# TLC5940ControlBoard.net
KiCad netlist of a schematic drawn in Altium Designer
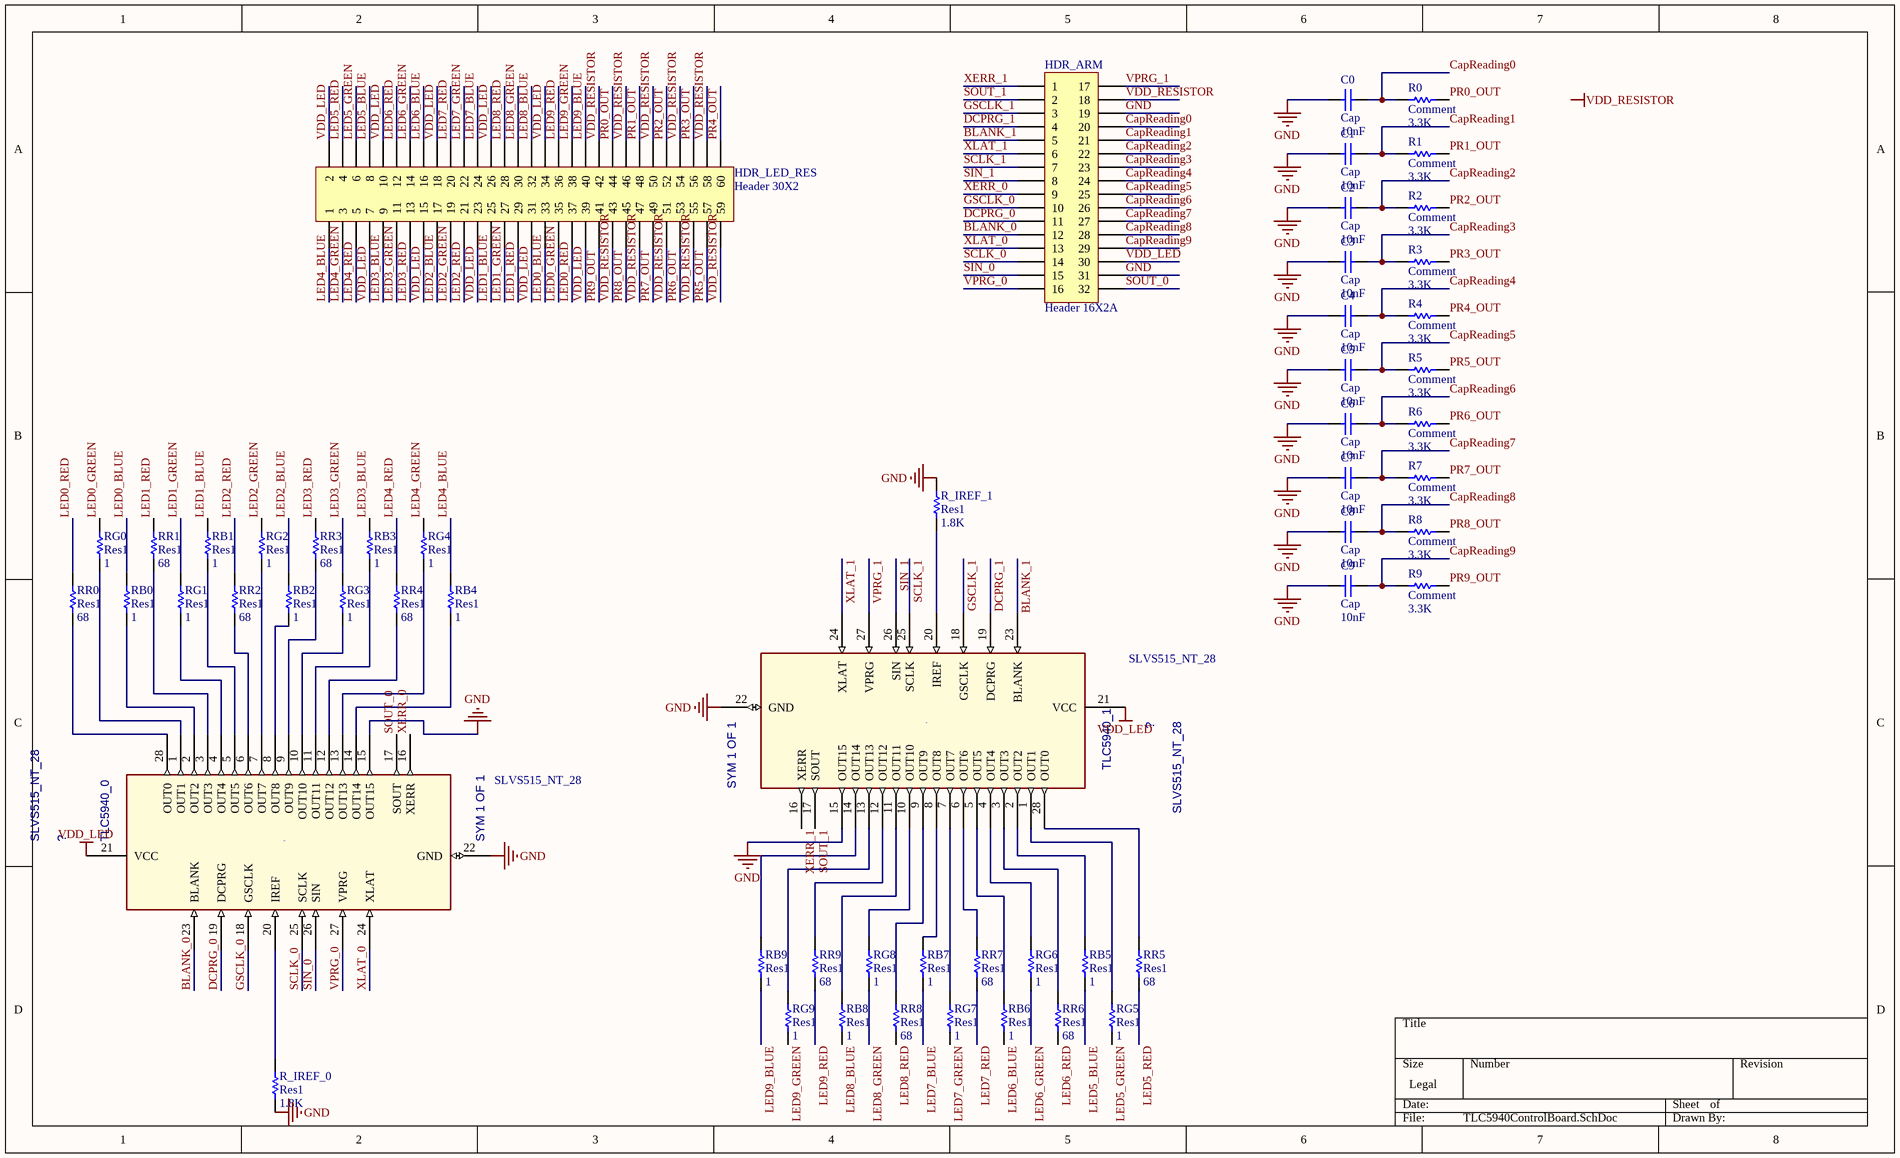
[diagram p0: TLC5940ControlBoard.SchDoc]

(export (version "E")
  (design (tool "Eeschema 10.0.6"))
  (components
    (comp (ref "C0")
      (value "Cap")
      (footprint "CAPR2.54-5.1x3.2")
      (description "Capacitor")
      (fields (field (name "ALTIUM_VALUE") "10nF") (field (name "PUBLISHER") "Altium Limited"))
      (libsource (lib "Miscellaneous Devices") (part "Cap"))
    )
    (comp (ref "C1")
      (value "Cap")
      (footprint "CAPR2.54-5.1x3.2")
      (description "Capacitor")
      (fields (field (name "ALTIUM_VALUE") "10nF") (field (name "PUBLISHER") "Altium Limited"))
      (libsource (lib "Miscellaneous Devices") (part "Cap"))
    )
    (comp (ref "C2")
      (value "Cap")
      (footprint "CAPR2.54-5.1x3.2")
      (description "Capacitor")
      (fields (field (name "ALTIUM_VALUE") "10nF") (field (name "PUBLISHER") "Altium Limited"))
      (libsource (lib "Miscellaneous Devices") (part "Cap"))
    )
    (comp (ref "C3")
      (value "Cap")
      (footprint "CAPR2.54-5.1x3.2")
      (description "Capacitor")
      (fields (field (name "ALTIUM_VALUE") "10nF") (field (name "PUBLISHER") "Altium Limited"))
      (libsource (lib "Miscellaneous Devices") (part "Cap"))
    )
    (comp (ref "C4")
      (value "Cap")
      (footprint "CAPR2.54-5.1x3.2")
      (description "Capacitor")
      (fields (field (name "ALTIUM_VALUE") "10nF") (field (name "PUBLISHER") "Altium Limited"))
      (libsource (lib "Miscellaneous Devices") (part "Cap"))
    )
    (comp (ref "C5")
      (value "Cap")
      (footprint "CAPR2.54-5.1x3.2")
      (description "Capacitor")
      (fields (field (name "ALTIUM_VALUE") "10nF") (field (name "PUBLISHER") "Altium Limited"))
      (libsource (lib "Miscellaneous Devices") (part "Cap"))
    )
    (comp (ref "C6")
      (value "Cap")
      (footprint "CAPR2.54-5.1x3.2")
      (description "Capacitor")
      (fields (field (name "ALTIUM_VALUE") "10nF") (field (name "PUBLISHER") "Altium Limited"))
      (libsource (lib "Miscellaneous Devices") (part "Cap"))
    )
    (comp (ref "C7")
      (value "Cap")
      (footprint "CAPR2.54-5.1x3.2")
      (description "Capacitor")
      (fields (field (name "ALTIUM_VALUE") "10nF") (field (name "PUBLISHER") "Altium Limited"))
      (libsource (lib "Miscellaneous Devices") (part "Cap"))
    )
    (comp (ref "C8")
      (value "Cap")
      (footprint "CAPR2.54-5.1x3.2")
      (description "Capacitor")
      (fields (field (name "ALTIUM_VALUE") "10nF") (field (name "PUBLISHER") "Altium Limited"))
      (libsource (lib "Miscellaneous Devices") (part "Cap"))
    )
    (comp (ref "C9")
      (value "Cap")
      (footprint "CAPR2.54-5.1x3.2")
      (description "Capacitor")
      (fields (field (name "ALTIUM_VALUE") "10nF") (field (name "PUBLISHER") "Altium Limited"))
      (libsource (lib "Miscellaneous Devices") (part "Cap"))
    )
    (comp (ref "HDR_ARM")
      (value "Header 16X2A")
      (footprint "HDR2X16_CEN")
      (description "Header, 16-Pin, Dual row")
      (fields (field (name "PUBLISHER") "Altium Limited"))
      (libsource (lib "Miscellaneous Connectors") (part "Header 16X2A"))
    )
    (comp (ref "HDR_LED_RES")
      (value "Header 30X2")
      (footprint "HDR2X30")
      (description "Header, 30-Pin, Dual row")
      (fields (field (name "PUBLISHER") "Altium Limited"))
      (libsource (lib "Miscellaneous Connectors") (part "Header 30X2"))
    )
    (comp (ref "R0")
      (value "Comment")
      (footprint "AXIAL-0.3")
      (description "Resistor")
      (fields (field (name "ALTIUM_VALUE") "3.3K") (field (name "PUBLISHER") "Altium Limited"))
      (libsource (lib "Miscellaneous Devices") (part "Res1"))
    )
    (comp (ref "R1")
      (value "Comment")
      (footprint "AXIAL-0.3")
      (description "Resistor")
      (fields (field (name "ALTIUM_VALUE") "3.3K") (field (name "PUBLISHER") "Altium Limited"))
      (libsource (lib "Miscellaneous Devices") (part "Res1"))
    )
    (comp (ref "R2")
      (value "Comment")
      (footprint "AXIAL-0.3")
      (description "Resistor")
      (fields (field (name "ALTIUM_VALUE") "3.3K") (field (name "PUBLISHER") "Altium Limited"))
      (libsource (lib "Miscellaneous Devices") (part "Res1"))
    )
    (comp (ref "R3")
      (value "Comment")
      (footprint "AXIAL-0.3")
      (description "Resistor")
      (fields (field (name "ALTIUM_VALUE") "3.3K") (field (name "PUBLISHER") "Altium Limited"))
      (libsource (lib "Miscellaneous Devices") (part "Res1"))
    )
    (comp (ref "R4")
      (value "Comment")
      (footprint "AXIAL-0.3")
      (description "Resistor")
      (fields (field (name "ALTIUM_VALUE") "3.3K") (field (name "PUBLISHER") "Altium Limited"))
      (libsource (lib "Miscellaneous Devices") (part "Res1"))
    )
    (comp (ref "R5")
      (value "Comment")
      (footprint "AXIAL-0.3")
      (description "Resistor")
      (fields (field (name "ALTIUM_VALUE") "3.3K") (field (name "PUBLISHER") "Altium Limited"))
      (libsource (lib "Miscellaneous Devices") (part "Res1"))
    )
    (comp (ref "R6")
      (value "Comment")
      (footprint "AXIAL-0.3")
      (description "Resistor")
      (fields (field (name "ALTIUM_VALUE") "3.3K") (field (name "PUBLISHER") "Altium Limited"))
      (libsource (lib "Miscellaneous Devices") (part "Res1"))
    )
    (comp (ref "R7")
      (value "Comment")
      (footprint "AXIAL-0.3")
      (description "Resistor")
      (fields (field (name "ALTIUM_VALUE") "3.3K") (field (name "PUBLISHER") "Altium Limited"))
      (libsource (lib "Miscellaneous Devices") (part "Res1"))
    )
    (comp (ref "R8")
      (value "Comment")
      (footprint "AXIAL-0.3")
      (description "Resistor")
      (fields (field (name "ALTIUM_VALUE") "3.3K") (field (name "PUBLISHER") "Altium Limited"))
      (libsource (lib "Miscellaneous Devices") (part "Res1"))
    )
    (comp (ref "R9")
      (value "Comment")
      (footprint "AXIAL-0.3")
      (description "Resistor")
      (fields (field (name "ALTIUM_VALUE") "3.3K") (field (name "PUBLISHER") "Altium Limited"))
      (libsource (lib "Miscellaneous Devices") (part "Res1"))
    )
    (comp (ref "RB0")
      (value "Res1")
      (footprint "AXIAL-0.3")
      (description "Resistor")
      (fields (field (name "ALTIUM_VALUE") "1") (field (name "PUBLISHER") "Altium Limited"))
      (libsource (lib "Miscellaneous Devices") (part "Res1"))
    )
    (comp (ref "RB1")
      (value "Res1")
      (footprint "AXIAL-0.3")
      (description "Resistor")
      (fields (field (name "ALTIUM_VALUE") "1") (field (name "PUBLISHER") "Altium Limited"))
      (libsource (lib "Miscellaneous Devices") (part "Res1"))
    )
    (comp (ref "RB2")
      (value "Res1")
      (footprint "AXIAL-0.3")
      (description "Resistor")
      (fields (field (name "ALTIUM_VALUE") "1") (field (name "PUBLISHER") "Altium Limited"))
      (libsource (lib "Miscellaneous Devices") (part "Res1"))
    )
    (comp (ref "RB3")
      (value "Res1")
      (footprint "AXIAL-0.3")
      (description "Resistor")
      (fields (field (name "ALTIUM_VALUE") "1") (field (name "PUBLISHER") "Altium Limited"))
      (libsource (lib "Miscellaneous Devices") (part "Res1"))
    )
    (comp (ref "RB4")
      (value "Res1")
      (footprint "AXIAL-0.3")
      (description "Resistor")
      (fields (field (name "ALTIUM_VALUE") "1") (field (name "PUBLISHER") "Altium Limited"))
      (libsource (lib "Miscellaneous Devices") (part "Res1"))
    )
    (comp (ref "RB5")
      (value "Res1")
      (footprint "AXIAL-0.3")
      (description "Resistor")
      (fields (field (name "ALTIUM_VALUE") "1") (field (name "PUBLISHER") "Altium Limited"))
      (libsource (lib "Miscellaneous Devices") (part "Res1"))
    )
    (comp (ref "RB6")
      (value "Res1")
      (footprint "AXIAL-0.3")
      (description "Resistor")
      (fields (field (name "ALTIUM_VALUE") "1") (field (name "PUBLISHER") "Altium Limited"))
      (libsource (lib "Miscellaneous Devices") (part "Res1"))
    )
    (comp (ref "RB7")
      (value "Res1")
      (footprint "AXIAL-0.3")
      (description "Resistor")
      (fields (field (name "ALTIUM_VALUE") "1") (field (name "PUBLISHER") "Altium Limited"))
      (libsource (lib "Miscellaneous Devices") (part "Res1"))
    )
    (comp (ref "RB8")
      (value "Res1")
      (footprint "AXIAL-0.3")
      (description "Resistor")
      (fields (field (name "ALTIUM_VALUE") "1") (field (name "PUBLISHER") "Altium Limited"))
      (libsource (lib "Miscellaneous Devices") (part "Res1"))
    )
    (comp (ref "RB9")
      (value "Res1")
      (footprint "AXIAL-0.3")
      (description "Resistor")
      (fields (field (name "ALTIUM_VALUE") "1") (field (name "PUBLISHER") "Altium Limited"))
      (libsource (lib "Miscellaneous Devices") (part "Res1"))
    )
    (comp (ref "RG0")
      (value "Res1")
      (footprint "AXIAL-0.3")
      (description "Resistor")
      (fields (field (name "ALTIUM_VALUE") "1") (field (name "PUBLISHER") "Altium Limited"))
      (libsource (lib "Miscellaneous Devices") (part "Res1"))
    )
    (comp (ref "RG1")
      (value "Res1")
      (footprint "AXIAL-0.3")
      (description "Resistor")
      (fields (field (name "ALTIUM_VALUE") "1") (field (name "PUBLISHER") "Altium Limited"))
      (libsource (lib "Miscellaneous Devices") (part "Res1"))
    )
    (comp (ref "RG2")
      (value "Res1")
      (footprint "AXIAL-0.3")
      (description "Resistor")
      (fields (field (name "ALTIUM_VALUE") "1") (field (name "PUBLISHER") "Altium Limited"))
      (libsource (lib "Miscellaneous Devices") (part "Res1"))
    )
    (comp (ref "RG3")
      (value "Res1")
      (footprint "AXIAL-0.3")
      (description "Resistor")
      (fields (field (name "ALTIUM_VALUE") "1") (field (name "PUBLISHER") "Altium Limited"))
      (libsource (lib "Miscellaneous Devices") (part "Res1"))
    )
    (comp (ref "RG4")
      (value "Res1")
      (footprint "AXIAL-0.3")
      (description "Resistor")
      (fields (field (name "ALTIUM_VALUE") "1") (field (name "PUBLISHER") "Altium Limited"))
      (libsource (lib "Miscellaneous Devices") (part "Res1"))
    )
    (comp (ref "RG5")
      (value "Res1")
      (footprint "AXIAL-0.3")
      (description "Resistor")
      (fields (field (name "ALTIUM_VALUE") "1") (field (name "PUBLISHER") "Altium Limited"))
      (libsource (lib "Miscellaneous Devices") (part "Res1"))
    )
    (comp (ref "RG6")
      (value "Res1")
      (footprint "AXIAL-0.3")
      (description "Resistor")
      (fields (field (name "ALTIUM_VALUE") "1") (field (name "PUBLISHER") "Altium Limited"))
      (libsource (lib "Miscellaneous Devices") (part "Res1"))
    )
    (comp (ref "RG7")
      (value "Res1")
      (footprint "AXIAL-0.3")
      (description "Resistor")
      (fields (field (name "ALTIUM_VALUE") "1") (field (name "PUBLISHER") "Altium Limited"))
      (libsource (lib "Miscellaneous Devices") (part "Res1"))
    )
    (comp (ref "RG8")
      (value "Res1")
      (footprint "AXIAL-0.3")
      (description "Resistor")
      (fields (field (name "ALTIUM_VALUE") "1") (field (name "PUBLISHER") "Altium Limited"))
      (libsource (lib "Miscellaneous Devices") (part "Res1"))
    )
    (comp (ref "RG9")
      (value "Res1")
      (footprint "AXIAL-0.3")
      (description "Resistor")
      (fields (field (name "ALTIUM_VALUE") "1") (field (name "PUBLISHER") "Altium Limited"))
      (libsource (lib "Miscellaneous Devices") (part "Res1"))
    )
    (comp (ref "RR0")
      (value "Res1")
      (footprint "AXIAL-0.3")
      (description "Resistor")
      (fields (field (name "ALTIUM_VALUE") "68") (field (name "PUBLISHER") "Altium Limited"))
      (libsource (lib "Miscellaneous Devices") (part "Res1"))
    )
    (comp (ref "RR1")
      (value "Res1")
      (footprint "AXIAL-0.3")
      (description "Resistor")
      (fields (field (name "ALTIUM_VALUE") "68") (field (name "PUBLISHER") "Altium Limited"))
      (libsource (lib "Miscellaneous Devices") (part "Res1"))
    )
    (comp (ref "RR2")
      (value "Res1")
      (footprint "AXIAL-0.3")
      (description "Resistor")
      (fields (field (name "ALTIUM_VALUE") "68") (field (name "PUBLISHER") "Altium Limited"))
      (libsource (lib "Miscellaneous Devices") (part "Res1"))
    )
    (comp (ref "RR3")
      (value "Res1")
      (footprint "AXIAL-0.3")
      (description "Resistor")
      (fields (field (name "ALTIUM_VALUE") "68") (field (name "PUBLISHER") "Altium Limited"))
      (libsource (lib "Miscellaneous Devices") (part "Res1"))
    )
    (comp (ref "RR4")
      (value "Res1")
      (footprint "AXIAL-0.3")
      (description "Resistor")
      (fields (field (name "ALTIUM_VALUE") "68") (field (name "PUBLISHER") "Altium Limited"))
      (libsource (lib "Miscellaneous Devices") (part "Res1"))
    )
    (comp (ref "RR5")
      (value "Res1")
      (footprint "AXIAL-0.3")
      (description "Resistor")
      (fields (field (name "ALTIUM_VALUE") "68") (field (name "PUBLISHER") "Altium Limited"))
      (libsource (lib "Miscellaneous Devices") (part "Res1"))
    )
    (comp (ref "RR6")
      (value "Res1")
      (footprint "AXIAL-0.3")
      (description "Resistor")
      (fields (field (name "ALTIUM_VALUE") "68") (field (name "PUBLISHER") "Altium Limited"))
      (libsource (lib "Miscellaneous Devices") (part "Res1"))
    )
    (comp (ref "RR7")
      (value "Res1")
      (footprint "AXIAL-0.3")
      (description "Resistor")
      (fields (field (name "ALTIUM_VALUE") "68") (field (name "PUBLISHER") "Altium Limited"))
      (libsource (lib "Miscellaneous Devices") (part "Res1"))
    )
    (comp (ref "RR8")
      (value "Res1")
      (footprint "AXIAL-0.3")
      (description "Resistor")
      (fields (field (name "ALTIUM_VALUE") "68") (field (name "PUBLISHER") "Altium Limited"))
      (libsource (lib "Miscellaneous Devices") (part "Res1"))
    )
    (comp (ref "RR9")
      (value "Res1")
      (footprint "AXIAL-0.3")
      (description "Resistor")
      (fields (field (name "ALTIUM_VALUE") "68") (field (name "PUBLISHER") "Altium Limited"))
      (libsource (lib "Miscellaneous Devices") (part "Res1"))
    )
    (comp (ref "R_IREF_0")
      (value "Res1")
      (footprint "AXIAL-0.3")
      (description "Resistor")
      (fields (field (name "ALTIUM_VALUE") "1.8K") (field (name "PUBLISHER") "Altium Limited"))
      (libsource (lib "Miscellaneous Devices") (part "Res1"))
    )
    (comp (ref "R_IREF_1")
      (value "Res1")
      (footprint "AXIAL-0.3")
      (description "Resistor")
      (fields (field (name "ALTIUM_VALUE") "1.8K") (field (name "PUBLISHER") "Altium Limited"))
      (libsource (lib "Miscellaneous Devices") (part "Res1"))
    )
    (comp (ref "TLC5940_0")
      (value "SLVS515_NT_28")
      (footprint "NT028")
      (fields
        (field (name "SYMNAME") "SLVS515_NT_28")
        (field (name "REFLOCATION") "?")
        (field (name "BOARDLOCATION") "?")
        (field (name "SLOTXOFY") "SYM 1 OF 1")
      )
      (libsource (lib "SLVS515_NT_28_Library") (part "SLVS515_NT_28"))
    )
    (comp (ref "TLC5940_1")
      (value "SLVS515_NT_28")
      (footprint "NT028")
      (fields
        (field (name "SYMNAME") "SLVS515_NT_28")
        (field (name "REFLOCATION") "?")
        (field (name "BOARDLOCATION") "?")
        (field (name "SLOTXOFY") "SYM 1 OF 1")
      )
      (libsource (lib "") (part "SLVS515_NT_28_1"))
    )
  )
  (nets
    (net (code "1") (name "/BLANK_0") (class "Default")
      (node (ref "HDR_ARM") (pin "12") (pinfunction "12_12") (pintype "passive"))
      (node (ref "TLC5940_0") (pin "23") (pinfunction "BLANK_23") (pintype "input"))
    )
    (net (code "2") (name "/BLANK_1") (class "Default")
      (node (ref "HDR_ARM") (pin "5") (pinfunction "5_5") (pintype "passive"))
      (node (ref "TLC5940_1") (pin "23") (pinfunction "BLANK_23") (pintype "input"))
    )
    (net (code "3") (name "/CapReading0") (class "Default")
      (node (ref "C0") (pin "2") (pinfunction "2_2") (pintype "passive"))
      (node (ref "HDR_ARM") (pin "20") (pinfunction "20_20") (pintype "passive"))
      (node (ref "R0") (pin "1") (pinfunction "1_1") (pintype "passive"))
    )
    (net (code "4") (name "/CapReading1") (class "Default")
      (node (ref "C1") (pin "2") (pinfunction "2_2") (pintype "passive"))
      (node (ref "HDR_ARM") (pin "21") (pinfunction "21_21") (pintype "passive"))
      (node (ref "R1") (pin "1") (pinfunction "1_1") (pintype "passive"))
    )
    (net (code "5") (name "/CapReading2") (class "Default")
      (node (ref "C2") (pin "2") (pinfunction "2_2") (pintype "passive"))
      (node (ref "HDR_ARM") (pin "22") (pinfunction "22_22") (pintype "passive"))
      (node (ref "R2") (pin "1") (pinfunction "1_1") (pintype "passive"))
    )
    (net (code "6") (name "/CapReading3") (class "Default")
      (node (ref "C3") (pin "2") (pinfunction "2_2") (pintype "passive"))
      (node (ref "HDR_ARM") (pin "23") (pinfunction "23_23") (pintype "passive"))
      (node (ref "R3") (pin "1") (pinfunction "1_1") (pintype "passive"))
    )
    (net (code "7") (name "/CapReading4") (class "Default")
      (node (ref "C4") (pin "2") (pinfunction "2_2") (pintype "passive"))
      (node (ref "HDR_ARM") (pin "24") (pinfunction "24_24") (pintype "passive"))
      (node (ref "R4") (pin "1") (pinfunction "1_1") (pintype "passive"))
    )
    (net (code "8") (name "/CapReading5") (class "Default")
      (node (ref "C5") (pin "2") (pinfunction "2_2") (pintype "passive"))
      (node (ref "HDR_ARM") (pin "25") (pinfunction "25_25") (pintype "passive"))
      (node (ref "R5") (pin "1") (pinfunction "1_1") (pintype "passive"))
    )
    (net (code "9") (name "/CapReading6") (class "Default")
      (node (ref "C6") (pin "2") (pinfunction "2_2") (pintype "passive"))
      (node (ref "HDR_ARM") (pin "26") (pinfunction "26_26") (pintype "passive"))
      (node (ref "R6") (pin "1") (pinfunction "1_1") (pintype "passive"))
    )
    (net (code "10") (name "/CapReading7") (class "Default")
      (node (ref "C7") (pin "2") (pinfunction "2_2") (pintype "passive"))
      (node (ref "HDR_ARM") (pin "27") (pinfunction "27_27") (pintype "passive"))
      (node (ref "R7") (pin "1") (pinfunction "1_1") (pintype "passive"))
    )
    (net (code "11") (name "/CapReading8") (class "Default")
      (node (ref "C8") (pin "2") (pinfunction "2_2") (pintype "passive"))
      (node (ref "HDR_ARM") (pin "28") (pinfunction "28_28") (pintype "passive"))
      (node (ref "R8") (pin "1") (pinfunction "1_1") (pintype "passive"))
    )
    (net (code "12") (name "/CapReading9") (class "Default")
      (node (ref "C9") (pin "2") (pinfunction "2_2") (pintype "passive"))
      (node (ref "HDR_ARM") (pin "29") (pinfunction "29_29") (pintype "passive"))
      (node (ref "R9") (pin "1") (pinfunction "1_1") (pintype "passive"))
    )
    (net (code "13") (name "/DCPRG_0") (class "Default")
      (node (ref "HDR_ARM") (pin "11") (pinfunction "11_11") (pintype "passive"))
      (node (ref "TLC5940_0") (pin "19") (pinfunction "DCPRG_19") (pintype "input"))
    )
    (net (code "14") (name "/DCPRG_1") (class "Default")
      (node (ref "HDR_ARM") (pin "4") (pinfunction "4_4") (pintype "passive"))
      (node (ref "TLC5940_1") (pin "19") (pinfunction "DCPRG_19") (pintype "input"))
    )
    (net (code "15") (name "/GSCLK_0") (class "Default")
      (node (ref "HDR_ARM") (pin "10") (pinfunction "10_10") (pintype "passive"))
      (node (ref "TLC5940_0") (pin "18") (pinfunction "GSCLK_18") (pintype "input"))
    )
    (net (code "16") (name "/GSCLK_1") (class "Default")
      (node (ref "HDR_ARM") (pin "3") (pinfunction "3_3") (pintype "passive"))
      (node (ref "TLC5940_1") (pin "18") (pinfunction "GSCLK_18") (pintype "input"))
    )
    (net (code "17") (name "/LED0_BLUE") (class "Default")
      (node (ref "HDR_LED_RES") (pin "33") (pinfunction "33_33") (pintype "passive"))
      (node (ref "RB0") (pin "2") (pinfunction "2_2") (pintype "passive"))
    )
    (net (code "18") (name "/LED0_GREEN") (class "Default")
      (node (ref "HDR_LED_RES") (pin "35") (pinfunction "35_35") (pintype "passive"))
      (node (ref "RG0") (pin "2") (pinfunction "2_2") (pintype "passive"))
    )
    (net (code "19") (name "/LED0_RED") (class "Default")
      (node (ref "HDR_LED_RES") (pin "37") (pinfunction "37_37") (pintype "passive"))
      (node (ref "RR0") (pin "2") (pinfunction "2_2") (pintype "passive"))
    )
    (net (code "20") (name "/LED1_BLUE") (class "Default")
      (node (ref "HDR_LED_RES") (pin "25") (pinfunction "25_25") (pintype "passive"))
      (node (ref "RB1") (pin "2") (pinfunction "2_2") (pintype "passive"))
    )
    (net (code "21") (name "/LED1_GREEN") (class "Default")
      (node (ref "HDR_LED_RES") (pin "27") (pinfunction "27_27") (pintype "passive"))
      (node (ref "RG1") (pin "2") (pinfunction "2_2") (pintype "passive"))
    )
    (net (code "22") (name "/LED1_RED") (class "Default")
      (node (ref "HDR_LED_RES") (pin "29") (pinfunction "29_29") (pintype "passive"))
      (node (ref "RR1") (pin "2") (pinfunction "2_2") (pintype "passive"))
    )
    (net (code "23") (name "/LED2_BLUE") (class "Default")
      (node (ref "HDR_LED_RES") (pin "17") (pinfunction "17_17") (pintype "passive"))
      (node (ref "RB2") (pin "2") (pinfunction "2_2") (pintype "passive"))
    )
    (net (code "24") (name "/LED2_GREEN") (class "Default")
      (node (ref "HDR_LED_RES") (pin "19") (pinfunction "19_19") (pintype "passive"))
      (node (ref "RG2") (pin "2") (pinfunction "2_2") (pintype "passive"))
    )
    (net (code "25") (name "/LED2_RED") (class "Default")
      (node (ref "HDR_LED_RES") (pin "21") (pinfunction "21_21") (pintype "passive"))
      (node (ref "RR2") (pin "2") (pinfunction "2_2") (pintype "passive"))
    )
    (net (code "26") (name "/LED3_BLUE") (class "Default")
      (node (ref "HDR_LED_RES") (pin "9") (pinfunction "9_9") (pintype "passive"))
      (node (ref "RB3") (pin "2") (pinfunction "2_2") (pintype "passive"))
    )
    (net (code "27") (name "/LED3_GREEN") (class "Default")
      (node (ref "HDR_LED_RES") (pin "11") (pinfunction "11_11") (pintype "passive"))
      (node (ref "RG3") (pin "2") (pinfunction "2_2") (pintype "passive"))
    )
    (net (code "28") (name "/LED3_RED") (class "Default")
      (node (ref "HDR_LED_RES") (pin "13") (pinfunction "13_13") (pintype "passive"))
      (node (ref "RR3") (pin "2") (pinfunction "2_2") (pintype "passive"))
    )
    (net (code "29") (name "/LED4_BLUE") (class "Default")
      (node (ref "HDR_LED_RES") (pin "1") (pinfunction "1_1") (pintype "passive"))
      (node (ref "RB4") (pin "2") (pinfunction "2_2") (pintype "passive"))
    )
    (net (code "30") (name "/LED4_GREEN") (class "Default")
      (node (ref "HDR_LED_RES") (pin "3") (pinfunction "3_3") (pintype "passive"))
      (node (ref "RG4") (pin "2") (pinfunction "2_2") (pintype "passive"))
    )
    (net (code "31") (name "/LED4_RED") (class "Default")
      (node (ref "HDR_LED_RES") (pin "5") (pinfunction "5_5") (pintype "passive"))
      (node (ref "RR4") (pin "2") (pinfunction "2_2") (pintype "passive"))
    )
    (net (code "32") (name "/LED5_BLUE") (class "Default")
      (node (ref "HDR_LED_RES") (pin "8") (pinfunction "8_8") (pintype "passive"))
      (node (ref "RB5") (pin "2") (pinfunction "2_2") (pintype "passive"))
    )
    (net (code "33") (name "/LED5_GREEN") (class "Default")
      (node (ref "HDR_LED_RES") (pin "6") (pinfunction "6_6") (pintype "passive"))
      (node (ref "RG5") (pin "2") (pinfunction "2_2") (pintype "passive"))
    )
    (net (code "34") (name "/LED5_RED") (class "Default")
      (node (ref "HDR_LED_RES") (pin "4") (pinfunction "4_4") (pintype "passive"))
      (node (ref "RR5") (pin "2") (pinfunction "2_2") (pintype "passive"))
    )
    (net (code "35") (name "/LED6_BLUE") (class "Default")
      (node (ref "HDR_LED_RES") (pin "16") (pinfunction "16_16") (pintype "passive"))
      (node (ref "RB6") (pin "2") (pinfunction "2_2") (pintype "passive"))
    )
    (net (code "36") (name "/LED6_GREEN") (class "Default")
      (node (ref "HDR_LED_RES") (pin "14") (pinfunction "14_14") (pintype "passive"))
      (node (ref "RG6") (pin "2") (pinfunction "2_2") (pintype "passive"))
    )
    (net (code "37") (name "/LED6_RED") (class "Default")
      (node (ref "HDR_LED_RES") (pin "12") (pinfunction "12_12") (pintype "passive"))
      (node (ref "RR6") (pin "2") (pinfunction "2_2") (pintype "passive"))
    )
    (net (code "38") (name "/LED7_BLUE") (class "Default")
      (node (ref "HDR_LED_RES") (pin "24") (pinfunction "24_24") (pintype "passive"))
      (node (ref "RB7") (pin "2") (pinfunction "2_2") (pintype "passive"))
    )
    (net (code "39") (name "/LED7_GREEN") (class "Default")
      (node (ref "HDR_LED_RES") (pin "22") (pinfunction "22_22") (pintype "passive"))
      (node (ref "RG7") (pin "2") (pinfunction "2_2") (pintype "passive"))
    )
    (net (code "40") (name "/LED7_RED") (class "Default")
      (node (ref "HDR_LED_RES") (pin "20") (pinfunction "20_20") (pintype "passive"))
      (node (ref "RR7") (pin "2") (pinfunction "2_2") (pintype "passive"))
    )
    (net (code "41") (name "/LED8_BLUE") (class "Default")
      (node (ref "HDR_LED_RES") (pin "32") (pinfunction "32_32") (pintype "passive"))
      (node (ref "RB8") (pin "2") (pinfunction "2_2") (pintype "passive"))
    )
    (net (code "42") (name "/LED8_GREEN") (class "Default")
      (node (ref "HDR_LED_RES") (pin "30") (pinfunction "30_30") (pintype "passive"))
      (node (ref "RG8") (pin "2") (pinfunction "2_2") (pintype "passive"))
    )
    (net (code "43") (name "/LED8_RED") (class "Default")
      (node (ref "HDR_LED_RES") (pin "28") (pinfunction "28_28") (pintype "passive"))
      (node (ref "RR8") (pin "2") (pinfunction "2_2") (pintype "passive"))
    )
    (net (code "44") (name "/LED9_BLUE") (class "Default")
      (node (ref "HDR_LED_RES") (pin "40") (pinfunction "40_40") (pintype "passive"))
      (node (ref "RB9") (pin "2") (pinfunction "2_2") (pintype "passive"))
    )
    (net (code "45") (name "/LED9_GREEN") (class "Default")
      (node (ref "HDR_LED_RES") (pin "38") (pinfunction "38_38") (pintype "passive"))
      (node (ref "RG9") (pin "2") (pinfunction "2_2") (pintype "passive"))
    )
    (net (code "46") (name "/LED9_RED") (class "Default")
      (node (ref "HDR_LED_RES") (pin "36") (pinfunction "36_36") (pintype "passive"))
      (node (ref "RR9") (pin "2") (pinfunction "2_2") (pintype "passive"))
    )
    (net (code "47") (name "/PR0_OUT") (class "Default")
      (node (ref "HDR_LED_RES") (pin "44") (pinfunction "44_44") (pintype "passive"))
      (node (ref "R0") (pin "2") (pinfunction "2_2") (pintype "passive"))
    )
    (net (code "48") (name "/PR1_OUT") (class "Default")
      (node (ref "HDR_LED_RES") (pin "48") (pinfunction "48_48") (pintype "passive"))
      (node (ref "R1") (pin "2") (pinfunction "2_2") (pintype "passive"))
    )
    (net (code "49") (name "/PR2_OUT") (class "Default")
      (node (ref "HDR_LED_RES") (pin "52") (pinfunction "52_52") (pintype "passive"))
      (node (ref "R2") (pin "2") (pinfunction "2_2") (pintype "passive"))
    )
    (net (code "50") (name "/PR3_OUT") (class "Default")
      (node (ref "HDR_LED_RES") (pin "56") (pinfunction "56_56") (pintype "passive"))
      (node (ref "R3") (pin "2") (pinfunction "2_2") (pintype "passive"))
    )
    (net (code "51") (name "/PR4_OUT") (class "Default")
      (node (ref "HDR_LED_RES") (pin "60") (pinfunction "60_60") (pintype "passive"))
      (node (ref "R4") (pin "2") (pinfunction "2_2") (pintype "passive"))
    )
    (net (code "52") (name "/PR5_OUT") (class "Default")
      (node (ref "HDR_LED_RES") (pin "57") (pinfunction "57_57") (pintype "passive"))
      (node (ref "R5") (pin "2") (pinfunction "2_2") (pintype "passive"))
    )
    (net (code "53") (name "/PR6_OUT") (class "Default")
      (node (ref "HDR_LED_RES") (pin "53") (pinfunction "53_53") (pintype "passive"))
      (node (ref "R6") (pin "2") (pinfunction "2_2") (pintype "passive"))
    )
    (net (code "54") (name "/PR7_OUT") (class "Default")
      (node (ref "HDR_LED_RES") (pin "49") (pinfunction "49_49") (pintype "passive"))
      (node (ref "R7") (pin "2") (pinfunction "2_2") (pintype "passive"))
    )
    (net (code "55") (name "/PR8_OUT") (class "Default")
      (node (ref "HDR_LED_RES") (pin "45") (pinfunction "45_45") (pintype "passive"))
      (node (ref "R8") (pin "2") (pinfunction "2_2") (pintype "passive"))
    )
    (net (code "56") (name "/PR9_OUT") (class "Default")
      (node (ref "HDR_LED_RES") (pin "41") (pinfunction "41_41") (pintype "passive"))
      (node (ref "R9") (pin "2") (pinfunction "2_2") (pintype "passive"))
    )
    (net (code "57") (name "/SCLK_0") (class "Default")
      (node (ref "HDR_ARM") (pin "14") (pinfunction "14_14") (pintype "passive"))
      (node (ref "TLC5940_0") (pin "25") (pinfunction "SCLK_25") (pintype "input"))
    )
    (net (code "58") (name "/SCLK_1") (class "Default")
      (node (ref "HDR_ARM") (pin "7") (pinfunction "7_7") (pintype "passive"))
      (node (ref "TLC5940_1") (pin "25") (pinfunction "SCLK_25") (pintype "input"))
    )
    (net (code "59") (name "/SIN_0") (class "Default")
      (node (ref "HDR_ARM") (pin "15") (pinfunction "15_15") (pintype "passive"))
      (node (ref "TLC5940_0") (pin "26") (pinfunction "SIN_26") (pintype "input"))
    )
    (net (code "60") (name "/SIN_1") (class "Default")
      (node (ref "HDR_ARM") (pin "8") (pinfunction "8_8") (pintype "passive"))
      (node (ref "TLC5940_1") (pin "26") (pinfunction "SIN_26") (pintype "input"))
    )
    (net (code "61") (name "/SOUT_0") (class "Default")
      (node (ref "HDR_ARM") (pin "32") (pinfunction "32_32") (pintype "passive"))
      (node (ref "TLC5940_0") (pin "17") (pinfunction "SOUT_17") (pintype "output"))
    )
    (net (code "62") (name "/SOUT_1") (class "Default")
      (node (ref "HDR_ARM") (pin "2") (pinfunction "2_2") (pintype "passive"))
      (node (ref "TLC5940_1") (pin "17") (pinfunction "SOUT_17") (pintype "output"))
    )
    (net (code "63") (name "/VPRG_0") (class "Default")
      (node (ref "HDR_ARM") (pin "16") (pinfunction "16_16") (pintype "passive"))
      (node (ref "TLC5940_0") (pin "27") (pinfunction "VPRG_27") (pintype "input"))
    )
    (net (code "64") (name "/VPRG_1") (class "Default")
      (node (ref "HDR_ARM") (pin "17") (pinfunction "17_17") (pintype "passive"))
      (node (ref "TLC5940_1") (pin "27") (pinfunction "VPRG_27") (pintype "input"))
    )
    (net (code "65") (name "/XERR_0") (class "Default")
      (node (ref "HDR_ARM") (pin "9") (pinfunction "9_9") (pintype "passive"))
      (node (ref "TLC5940_0") (pin "16") (pinfunction "XERR_16") (pintype "output"))
    )
    (net (code "66") (name "/XERR_1") (class "Default")
      (node (ref "HDR_ARM") (pin "1") (pinfunction "1_1") (pintype "passive"))
      (node (ref "TLC5940_1") (pin "16") (pinfunction "XERR_16") (pintype "output"))
    )
    (net (code "67") (name "/XLAT_0") (class "Default")
      (node (ref "HDR_ARM") (pin "13") (pinfunction "13_13") (pintype "passive"))
      (node (ref "TLC5940_0") (pin "24") (pinfunction "XLAT_24") (pintype "input"))
    )
    (net (code "68") (name "/XLAT_1") (class "Default")
      (node (ref "HDR_ARM") (pin "6") (pinfunction "6_6") (pintype "passive"))
      (node (ref "TLC5940_1") (pin "24") (pinfunction "XLAT_24") (pintype "input"))
    )
    (net (code "69") (name "GND") (class "Default")
      (node (ref "C0") (pin "1") (pinfunction "1_1") (pintype "passive"))
      (node (ref "C1") (pin "1") (pinfunction "1_1") (pintype "passive"))
      (node (ref "C2") (pin "1") (pinfunction "1_1") (pintype "passive"))
      (node (ref "C3") (pin "1") (pinfunction "1_1") (pintype "passive"))
      (node (ref "C4") (pin "1") (pinfunction "1_1") (pintype "passive"))
      (node (ref "C5") (pin "1") (pinfunction "1_1") (pintype "passive"))
      (node (ref "C6") (pin "1") (pinfunction "1_1") (pintype "passive"))
      (node (ref "C7") (pin "1") (pinfunction "1_1") (pintype "passive"))
      (node (ref "C8") (pin "1") (pinfunction "1_1") (pintype "passive"))
      (node (ref "C9") (pin "1") (pinfunction "1_1") (pintype "passive"))
      (node (ref "HDR_ARM") (pin "19") (pinfunction "19_19") (pintype "passive"))
      (node (ref "HDR_ARM") (pin "31") (pinfunction "31_31") (pintype "passive"))
      (node (ref "R_IREF_0") (pin "1") (pinfunction "1_1") (pintype "passive"))
      (node (ref "R_IREF_1") (pin "1") (pinfunction "1_1") (pintype "passive"))
      (node (ref "TLC5940_0") (pin "15") (pinfunction "OUT15_15") (pintype "output"))
      (node (ref "TLC5940_0") (pin "22") (pinfunction "GND_22") (pintype "bidirectional"))
      (node (ref "TLC5940_1") (pin "15") (pinfunction "OUT15_15") (pintype "output"))
      (node (ref "TLC5940_1") (pin "22") (pinfunction "GND_22") (pintype "bidirectional"))
    )
    (net (code "70") (name "Net-(TLC5940_0-IREF)") (class "Default")
      (node (ref "R_IREF_0") (pin "2") (pinfunction "2_2") (pintype "passive"))
      (node (ref "TLC5940_0") (pin "20") (pinfunction "IREF_20") (pintype "input"))
    )
    (net (code "71") (name "Net-(TLC5940_0-OUT0)") (class "Default")
      (node (ref "RR0") (pin "1") (pinfunction "1_1") (pintype "passive"))
      (node (ref "TLC5940_0") (pin "28") (pinfunction "OUT0_28") (pintype "output"))
    )
    (net (code "72") (name "Net-(TLC5940_0-OUT1)") (class "Default")
      (node (ref "RG0") (pin "1") (pinfunction "1_1") (pintype "passive"))
      (node (ref "TLC5940_0") (pin "1") (pinfunction "OUT1_1") (pintype "output"))
    )
    (net (code "73") (name "Net-(TLC5940_0-OUT2)") (class "Default")
      (node (ref "RB0") (pin "1") (pinfunction "1_1") (pintype "passive"))
      (node (ref "TLC5940_0") (pin "2") (pinfunction "OUT2_2") (pintype "output"))
    )
    (net (code "74") (name "Net-(TLC5940_0-OUT3)") (class "Default")
      (node (ref "RR1") (pin "1") (pinfunction "1_1") (pintype "passive"))
      (node (ref "TLC5940_0") (pin "3") (pinfunction "OUT3_3") (pintype "output"))
    )
    (net (code "75") (name "Net-(TLC5940_0-OUT4)") (class "Default")
      (node (ref "RG1") (pin "1") (pinfunction "1_1") (pintype "passive"))
      (node (ref "TLC5940_0") (pin "4") (pinfunction "OUT4_4") (pintype "output"))
    )
    (net (code "76") (name "Net-(TLC5940_0-OUT5)") (class "Default")
      (node (ref "RB1") (pin "1") (pinfunction "1_1") (pintype "passive"))
      (node (ref "TLC5940_0") (pin "5") (pinfunction "OUT5_5") (pintype "output"))
    )
    (net (code "77") (name "Net-(TLC5940_0-OUT6)") (class "Default")
      (node (ref "RR2") (pin "1") (pinfunction "1_1") (pintype "passive"))
      (node (ref "TLC5940_0") (pin "6") (pinfunction "OUT6_6") (pintype "output"))
    )
    (net (code "78") (name "Net-(TLC5940_0-OUT7)") (class "Default")
      (node (ref "RG2") (pin "1") (pinfunction "1_1") (pintype "passive"))
      (node (ref "TLC5940_0") (pin "7") (pinfunction "OUT7_7") (pintype "output"))
    )
    (net (code "79") (name "Net-(TLC5940_0-OUT8)") (class "Default")
      (node (ref "RB2") (pin "1") (pinfunction "1_1") (pintype "passive"))
      (node (ref "TLC5940_0") (pin "8") (pinfunction "OUT8_8") (pintype "output"))
    )
    (net (code "80") (name "Net-(TLC5940_0-OUT9)") (class "Default")
      (node (ref "RR3") (pin "1") (pinfunction "1_1") (pintype "passive"))
      (node (ref "TLC5940_0") (pin "9") (pinfunction "OUT9_9") (pintype "output"))
    )
    (net (code "81") (name "Net-(TLC5940_0-OUT10)") (class "Default")
      (node (ref "RG3") (pin "1") (pinfunction "1_1") (pintype "passive"))
      (node (ref "TLC5940_0") (pin "10") (pinfunction "OUT10_10") (pintype "output"))
    )
    (net (code "82") (name "Net-(TLC5940_0-OUT11)") (class "Default")
      (node (ref "RB3") (pin "1") (pinfunction "1_1") (pintype "passive"))
      (node (ref "TLC5940_0") (pin "11") (pinfunction "OUT11_11") (pintype "output"))
    )
    (net (code "83") (name "Net-(TLC5940_0-OUT12)") (class "Default")
      (node (ref "RR4") (pin "1") (pinfunction "1_1") (pintype "passive"))
      (node (ref "TLC5940_0") (pin "12") (pinfunction "OUT12_12") (pintype "output"))
    )
    (net (code "84") (name "Net-(TLC5940_0-OUT13)") (class "Default")
      (node (ref "RG4") (pin "1") (pinfunction "1_1") (pintype "passive"))
      (node (ref "TLC5940_0") (pin "13") (pinfunction "OUT13_13") (pintype "output"))
    )
    (net (code "85") (name "Net-(TLC5940_0-OUT14)") (class "Default")
      (node (ref "RB4") (pin "1") (pinfunction "1_1") (pintype "passive"))
      (node (ref "TLC5940_0") (pin "14") (pinfunction "OUT14_14") (pintype "output"))
    )
    (net (code "86") (name "Net-(TLC5940_1-IREF)") (class "Default")
      (node (ref "R_IREF_1") (pin "2") (pinfunction "2_2") (pintype "passive"))
      (node (ref "TLC5940_1") (pin "20") (pinfunction "IREF_20") (pintype "input"))
    )
    (net (code "87") (name "Net-(TLC5940_1-OUT0)") (class "Default")
      (node (ref "RR5") (pin "1") (pinfunction "1_1") (pintype "passive"))
      (node (ref "TLC5940_1") (pin "28") (pinfunction "OUT0_28") (pintype "output"))
    )
    (net (code "88") (name "Net-(TLC5940_1-OUT1)") (class "Default")
      (node (ref "RG5") (pin "1") (pinfunction "1_1") (pintype "passive"))
      (node (ref "TLC5940_1") (pin "1") (pinfunction "OUT1_1") (pintype "output"))
    )
    (net (code "89") (name "Net-(TLC5940_1-OUT2)") (class "Default")
      (node (ref "RB5") (pin "1") (pinfunction "1_1") (pintype "passive"))
      (node (ref "TLC5940_1") (pin "2") (pinfunction "OUT2_2") (pintype "output"))
    )
    (net (code "90") (name "Net-(TLC5940_1-OUT3)") (class "Default")
      (node (ref "RR6") (pin "1") (pinfunction "1_1") (pintype "passive"))
      (node (ref "TLC5940_1") (pin "3") (pinfunction "OUT3_3") (pintype "output"))
    )
    (net (code "91") (name "Net-(TLC5940_1-OUT4)") (class "Default")
      (node (ref "RG6") (pin "1") (pinfunction "1_1") (pintype "passive"))
      (node (ref "TLC5940_1") (pin "4") (pinfunction "OUT4_4") (pintype "output"))
    )
    (net (code "92") (name "Net-(TLC5940_1-OUT5)") (class "Default")
      (node (ref "RB6") (pin "1") (pinfunction "1_1") (pintype "passive"))
      (node (ref "TLC5940_1") (pin "5") (pinfunction "OUT5_5") (pintype "output"))
    )
    (net (code "93") (name "Net-(TLC5940_1-OUT6)") (class "Default")
      (node (ref "RR7") (pin "1") (pinfunction "1_1") (pintype "passive"))
      (node (ref "TLC5940_1") (pin "6") (pinfunction "OUT6_6") (pintype "output"))
    )
    (net (code "94") (name "Net-(TLC5940_1-OUT7)") (class "Default")
      (node (ref "RG7") (pin "1") (pinfunction "1_1") (pintype "passive"))
      (node (ref "TLC5940_1") (pin "7") (pinfunction "OUT7_7") (pintype "output"))
    )
    (net (code "95") (name "Net-(TLC5940_1-OUT8)") (class "Default")
      (node (ref "RB7") (pin "1") (pinfunction "1_1") (pintype "passive"))
      (node (ref "TLC5940_1") (pin "8") (pinfunction "OUT8_8") (pintype "output"))
    )
    (net (code "96") (name "Net-(TLC5940_1-OUT9)") (class "Default")
      (node (ref "RR8") (pin "1") (pinfunction "1_1") (pintype "passive"))
      (node (ref "TLC5940_1") (pin "9") (pinfunction "OUT9_9") (pintype "output"))
    )
    (net (code "97") (name "Net-(TLC5940_1-OUT10)") (class "Default")
      (node (ref "RG8") (pin "1") (pinfunction "1_1") (pintype "passive"))
      (node (ref "TLC5940_1") (pin "10") (pinfunction "OUT10_10") (pintype "output"))
    )
    (net (code "98") (name "Net-(TLC5940_1-OUT11)") (class "Default")
      (node (ref "RB8") (pin "1") (pinfunction "1_1") (pintype "passive"))
      (node (ref "TLC5940_1") (pin "11") (pinfunction "OUT11_11") (pintype "output"))
    )
    (net (code "99") (name "Net-(TLC5940_1-OUT12)") (class "Default")
      (node (ref "RR9") (pin "1") (pinfunction "1_1") (pintype "passive"))
      (node (ref "TLC5940_1") (pin "12") (pinfunction "OUT12_12") (pintype "output"))
    )
    (net (code "100") (name "Net-(TLC5940_1-OUT13)") (class "Default")
      (node (ref "RG9") (pin "1") (pinfunction "1_1") (pintype "passive"))
      (node (ref "TLC5940_1") (pin "13") (pinfunction "OUT13_13") (pintype "output"))
    )
    (net (code "101") (name "Net-(TLC5940_1-OUT14)") (class "Default")
      (node (ref "RB9") (pin "1") (pinfunction "1_1") (pintype "passive"))
      (node (ref "TLC5940_1") (pin "14") (pinfunction "OUT14_14") (pintype "output"))
    )
    (net (code "102") (name "VDD_LED") (class "Default")
      (node (ref "HDR_ARM") (pin "30") (pinfunction "30_30") (pintype "passive"))
      (node (ref "HDR_LED_RES") (pin "10") (pinfunction "10_10") (pintype "passive"))
      (node (ref "HDR_LED_RES") (pin "15") (pinfunction "15_15") (pintype "passive"))
      (node (ref "HDR_LED_RES") (pin "18") (pinfunction "18_18") (pintype "passive"))
      (node (ref "HDR_LED_RES") (pin "2") (pinfunction "2_2") (pintype "passive"))
      (node (ref "HDR_LED_RES") (pin "23") (pinfunction "23_23") (pintype "passive"))
      (node (ref "HDR_LED_RES") (pin "26") (pinfunction "26_26") (pintype "passive"))
      (node (ref "HDR_LED_RES") (pin "31") (pinfunction "31_31") (pintype "passive"))
      (node (ref "HDR_LED_RES") (pin "34") (pinfunction "34_34") (pintype "passive"))
      (node (ref "HDR_LED_RES") (pin "39") (pinfunction "39_39") (pintype "passive"))
      (node (ref "HDR_LED_RES") (pin "7") (pinfunction "7_7") (pintype "passive"))
      (node (ref "TLC5940_0") (pin "21") (pinfunction "VCC_21") (pintype "power_in"))
      (node (ref "TLC5940_1") (pin "21") (pinfunction "VCC_21") (pintype "power_in"))
    )
    (net (code "103") (name "VDD_RESISTOR") (class "Default")
      (node (ref "HDR_ARM") (pin "18") (pinfunction "18_18") (pintype "passive"))
      (node (ref "HDR_LED_RES") (pin "42") (pinfunction "42_42") (pintype "passive"))
      (node (ref "HDR_LED_RES") (pin "43") (pinfunction "43_43") (pintype "passive"))
      (node (ref "HDR_LED_RES") (pin "46") (pinfunction "46_46") (pintype "passive"))
      (node (ref "HDR_LED_RES") (pin "47") (pinfunction "47_47") (pintype "passive"))
      (node (ref "HDR_LED_RES") (pin "50") (pinfunction "50_50") (pintype "passive"))
      (node (ref "HDR_LED_RES") (pin "51") (pinfunction "51_51") (pintype "passive"))
      (node (ref "HDR_LED_RES") (pin "54") (pinfunction "54_54") (pintype "passive"))
      (node (ref "HDR_LED_RES") (pin "55") (pinfunction "55_55") (pintype "passive"))
      (node (ref "HDR_LED_RES") (pin "58") (pinfunction "58_58") (pintype "passive"))
      (node (ref "HDR_LED_RES") (pin "59") (pinfunction "59_59") (pintype "passive"))
    )
  )
)
